# bb_header.net
KiCad netlist of a schematic drawn in Altium Designer
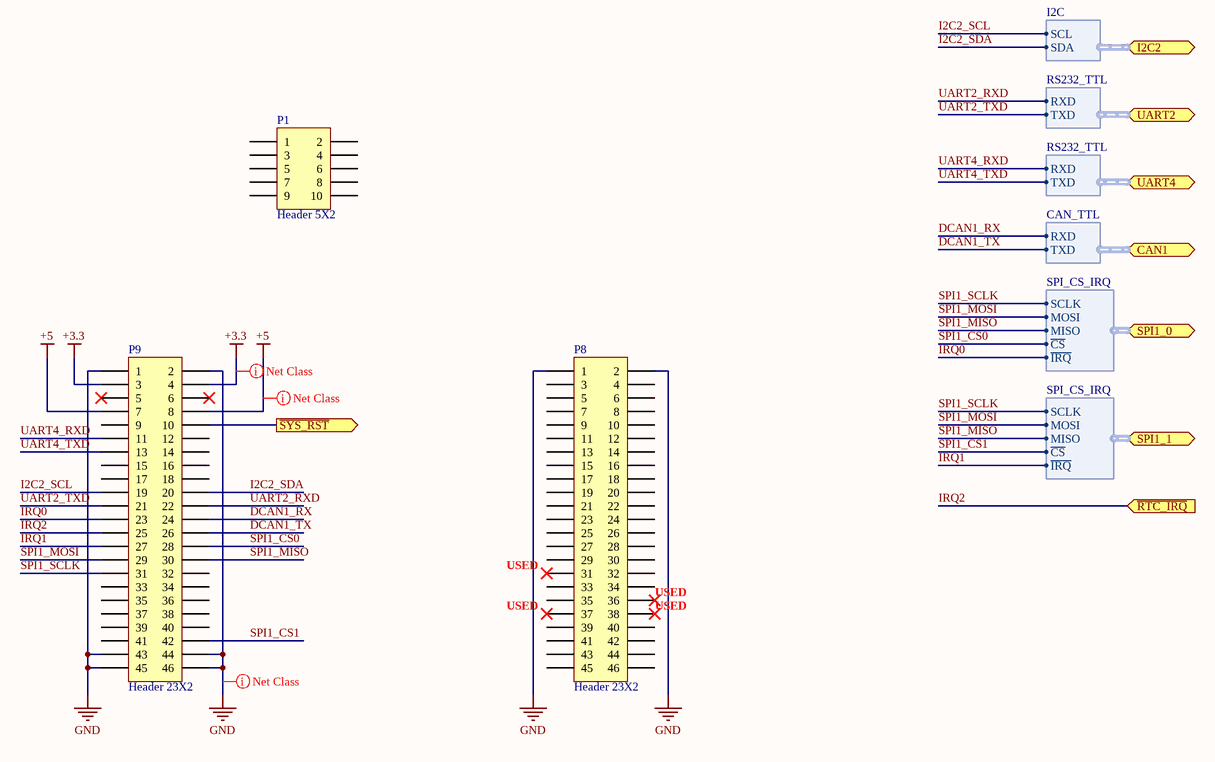
[diagram p0: bb header.SchDoc]

(export (version "E")
  (design (tool "Eeschema 10.0.6"))
  (components
    (comp (ref "P1")
      (value "Header 5X2")
      (footprint "TSW-105-07-T-D_DOWN")
      (description "Header, 5-Pin, Dual row")
      (fields (field (name "PUBLISHER") "Altium Limited"))
      (libsource (lib "Miscellaneous Connectors") (part "Header 5X2"))
    )
    (comp (ref "P8")
      (value "Header 23X2")
      (footprint "TSW-123-07-T-D_DOWN")
      (description "Header, 23-Pin, Dual row")
      (fields (field (name "PUBLISHER") "Altium Limited"))
      (libsource (lib "23x2 header") (part "Header 23X2"))
    )
    (comp (ref "P9")
      (value "Header 23X2")
      (footprint "TSW-123-07-T-D_DOWN")
      (description "Header, 23-Pin, Dual row")
      (fields (field (name "PUBLISHER") "Altium Limited"))
      (libsource (lib "23x2 header") (part "Header 23X2"))
    )
  )
  (nets
    (net (code "5") (name "+3.3") (class "Default")
      (node (ref "P9") (pin "3") (pinfunction "3_3") (pintype "passive"))
      (node (ref "P9") (pin "4") (pinfunction "4_4") (pintype "passive"))
    )
    (net (code "6") (name "+5") (class "Default")
      (node (ref "P9") (pin "7") (pinfunction "7_7") (pintype "passive"))
      (node (ref "P9") (pin "8") (pinfunction "8_8") (pintype "passive"))
    )
    (net (code "7") (name "/DCAN1_RX") (class "Default")
      (node (ref "P9") (pin "24") (pinfunction "24_24") (pintype "passive"))
    )
    (net (code "8") (name "/DCAN1_TX") (class "Default")
      (node (ref "P9") (pin "26") (pinfunction "26_26") (pintype "passive"))
    )
    (net (code "9") (name "/I2C2_SCL") (class "Default")
      (node (ref "P9") (pin "19") (pinfunction "19_19") (pintype "passive"))
    )
    (net (code "10") (name "/I2C2_SDA") (class "Default")
      (node (ref "P9") (pin "20") (pinfunction "20_20") (pintype "passive"))
    )
    (net (code "11") (name "/IRQ0") (class "Default")
      (node (ref "P9") (pin "23") (pinfunction "23_23") (pintype "passive"))
    )
    (net (code "12") (name "/IRQ1") (class "Default")
      (node (ref "P9") (pin "27") (pinfunction "27_27") (pintype "passive"))
    )
    (net (code "13") (name "/IRQ2") (class "Default")
      (node (ref "P9") (pin "25") (pinfunction "25_25") (pintype "passive"))
    )
    (net (code "14") (name "/SPI1_CS0") (class "Default")
      (node (ref "P9") (pin "28") (pinfunction "28_28") (pintype "passive"))
    )
    (net (code "15") (name "/SPI1_CS1") (class "Default")
      (node (ref "P9") (pin "42") (pinfunction "42_42") (pintype "passive"))
    )
    (net (code "16") (name "/SPI1_MISO") (class "Default")
      (node (ref "P9") (pin "30") (pinfunction "30_30") (pintype "passive"))
    )
    (net (code "17") (name "/SPI1_MOSI") (class "Default")
      (node (ref "P9") (pin "29") (pinfunction "29_29") (pintype "passive"))
    )
    (net (code "18") (name "/SPI1_SCLK") (class "Default")
      (node (ref "P9") (pin "31") (pinfunction "31_31") (pintype "passive"))
    )
    (net (code "19") (name "/UART2_RXD") (class "Default")
      (node (ref "P9") (pin "22") (pinfunction "22_22") (pintype "passive"))
    )
    (net (code "20") (name "/UART2_TXD") (class "Default")
      (node (ref "P9") (pin "21") (pinfunction "21_21") (pintype "passive"))
    )
    (net (code "21") (name "/UART4_RXD") (class "Default")
      (node (ref "P9") (pin "11") (pinfunction "11_11") (pintype "passive"))
    )
    (net (code "22") (name "/UART4_TXD") (class "Default")
      (node (ref "P9") (pin "13") (pinfunction "13_13") (pintype "passive"))
    )
    (net (code "27") (name "/~{SYS_RST}") (class "Default")
      (node (ref "P9") (pin "10") (pinfunction "10_10") (pintype "passive"))
    )
    (net (code "28") (name "GND") (class "Default")
      (node (ref "P8") (pin "1") (pinfunction "1_1") (pintype "passive"))
      (node (ref "P8") (pin "2") (pinfunction "2_2") (pintype "passive"))
      (node (ref "P9") (pin "1") (pinfunction "1_1") (pintype "passive"))
      (node (ref "P9") (pin "2") (pinfunction "2_2") (pintype "passive"))
      (node (ref "P9") (pin "43") (pinfunction "43_43") (pintype "passive"))
      (node (ref "P9") (pin "44") (pinfunction "44_44") (pintype "passive"))
      (node (ref "P9") (pin "45") (pinfunction "45_45") (pintype "passive"))
      (node (ref "P9") (pin "46") (pinfunction "46_46") (pintype "passive"))
    )
    (net (code "29") (name "unconnected-(P1-Pad1)") (class "Default")
      (node (ref "P1") (pin "1") (pinfunction "1_1") (pintype "passive"))
    )
    (net (code "30") (name "unconnected-(P1-Pad2)") (class "Default")
      (node (ref "P1") (pin "2") (pinfunction "2_2") (pintype "passive"))
    )
    (net (code "31") (name "unconnected-(P1-Pad3)") (class "Default")
      (node (ref "P1") (pin "3") (pinfunction "3_3") (pintype "passive"))
    )
    (net (code "32") (name "unconnected-(P1-Pad4)") (class "Default")
      (node (ref "P1") (pin "4") (pinfunction "4_4") (pintype "passive"))
    )
    (net (code "33") (name "unconnected-(P1-Pad5)") (class "Default")
      (node (ref "P1") (pin "5") (pinfunction "5_5") (pintype "passive"))
    )
    (net (code "34") (name "unconnected-(P1-Pad6)") (class "Default")
      (node (ref "P1") (pin "6") (pinfunction "6_6") (pintype "passive"))
    )
    (net (code "35") (name "unconnected-(P1-Pad7)") (class "Default")
      (node (ref "P1") (pin "7") (pinfunction "7_7") (pintype "passive"))
    )
    (net (code "36") (name "unconnected-(P1-Pad8)") (class "Default")
      (node (ref "P1") (pin "8") (pinfunction "8_8") (pintype "passive"))
    )
    (net (code "37") (name "unconnected-(P1-Pad9)") (class "Default")
      (node (ref "P1") (pin "9") (pinfunction "9_9") (pintype "passive"))
    )
    (net (code "38") (name "unconnected-(P1-Pad10)") (class "Default")
      (node (ref "P1") (pin "10") (pinfunction "10_10") (pintype "passive"))
    )
    (net (code "39") (name "unconnected-(P8-Pad3)") (class "Default")
      (node (ref "P8") (pin "3") (pinfunction "3_3") (pintype "passive"))
    )
    (net (code "40") (name "unconnected-(P8-Pad4)") (class "Default")
      (node (ref "P8") (pin "4") (pinfunction "4_4") (pintype "passive"))
    )
    (net (code "41") (name "unconnected-(P8-Pad5)") (class "Default")
      (node (ref "P8") (pin "5") (pinfunction "5_5") (pintype "passive"))
    )
    (net (code "42") (name "unconnected-(P8-Pad6)") (class "Default")
      (node (ref "P8") (pin "6") (pinfunction "6_6") (pintype "passive"))
    )
    (net (code "43") (name "unconnected-(P8-Pad7)") (class "Default")
      (node (ref "P8") (pin "7") (pinfunction "7_7") (pintype "passive"))
    )
    (net (code "44") (name "unconnected-(P8-Pad8)") (class "Default")
      (node (ref "P8") (pin "8") (pinfunction "8_8") (pintype "passive"))
    )
    (net (code "45") (name "unconnected-(P8-Pad9)") (class "Default")
      (node (ref "P8") (pin "9") (pinfunction "9_9") (pintype "passive"))
    )
    (net (code "46") (name "unconnected-(P8-Pad10)") (class "Default")
      (node (ref "P8") (pin "10") (pinfunction "10_10") (pintype "passive"))
    )
    (net (code "47") (name "unconnected-(P8-Pad11)") (class "Default")
      (node (ref "P8") (pin "11") (pinfunction "11_11") (pintype "passive"))
    )
    (net (code "48") (name "unconnected-(P8-Pad12)") (class "Default")
      (node (ref "P8") (pin "12") (pinfunction "12_12") (pintype "passive"))
    )
    (net (code "49") (name "unconnected-(P8-Pad13)") (class "Default")
      (node (ref "P8") (pin "13") (pinfunction "13_13") (pintype "passive"))
    )
    (net (code "50") (name "unconnected-(P8-Pad14)") (class "Default")
      (node (ref "P8") (pin "14") (pinfunction "14_14") (pintype "passive"))
    )
    (net (code "51") (name "unconnected-(P8-Pad15)") (class "Default")
      (node (ref "P8") (pin "15") (pinfunction "15_15") (pintype "passive"))
    )
    (net (code "52") (name "unconnected-(P8-Pad16)") (class "Default")
      (node (ref "P8") (pin "16") (pinfunction "16_16") (pintype "passive"))
    )
    (net (code "53") (name "unconnected-(P8-Pad17)") (class "Default")
      (node (ref "P8") (pin "17") (pinfunction "17_17") (pintype "passive"))
    )
    (net (code "54") (name "unconnected-(P8-Pad18)") (class "Default")
      (node (ref "P8") (pin "18") (pinfunction "18_18") (pintype "passive"))
    )
    (net (code "55") (name "unconnected-(P8-Pad19)") (class "Default")
      (node (ref "P8") (pin "19") (pinfunction "19_19") (pintype "passive"))
    )
    (net (code "56") (name "unconnected-(P8-Pad20)") (class "Default")
      (node (ref "P8") (pin "20") (pinfunction "20_20") (pintype "passive"))
    )
    (net (code "57") (name "unconnected-(P8-Pad21)") (class "Default")
      (node (ref "P8") (pin "21") (pinfunction "21_21") (pintype "passive"))
    )
    (net (code "58") (name "unconnected-(P8-Pad22)") (class "Default")
      (node (ref "P8") (pin "22") (pinfunction "22_22") (pintype "passive"))
    )
    (net (code "59") (name "unconnected-(P8-Pad23)") (class "Default")
      (node (ref "P8") (pin "23") (pinfunction "23_23") (pintype "passive"))
    )
    (net (code "60") (name "unconnected-(P8-Pad24)") (class "Default")
      (node (ref "P8") (pin "24") (pinfunction "24_24") (pintype "passive"))
    )
    (net (code "61") (name "unconnected-(P8-Pad25)") (class "Default")
      (node (ref "P8") (pin "25") (pinfunction "25_25") (pintype "passive"))
    )
    (net (code "62") (name "unconnected-(P8-Pad26)") (class "Default")
      (node (ref "P8") (pin "26") (pinfunction "26_26") (pintype "passive"))
    )
    (net (code "63") (name "unconnected-(P8-Pad27)") (class "Default")
      (node (ref "P8") (pin "27") (pinfunction "27_27") (pintype "passive"))
    )
    (net (code "64") (name "unconnected-(P8-Pad28)") (class "Default")
      (node (ref "P8") (pin "28") (pinfunction "28_28") (pintype "passive"))
    )
    (net (code "65") (name "unconnected-(P8-Pad29)") (class "Default")
      (node (ref "P8") (pin "29") (pinfunction "29_29") (pintype "passive"))
    )
    (net (code "66") (name "unconnected-(P8-Pad30)") (class "Default")
      (node (ref "P8") (pin "30") (pinfunction "30_30") (pintype "passive"))
    )
    (net (code "67") (name "unconnected-(P8-Pad31)") (class "Default")
      (node (ref "P8") (pin "31") (pinfunction "31_31") (pintype "passive+no_connect"))
    )
    (net (code "68") (name "unconnected-(P8-Pad32)") (class "Default")
      (node (ref "P8") (pin "32") (pinfunction "32_32") (pintype "passive"))
    )
    (net (code "69") (name "unconnected-(P8-Pad33)") (class "Default")
      (node (ref "P8") (pin "33") (pinfunction "33_33") (pintype "passive"))
    )
    (net (code "70") (name "unconnected-(P8-Pad34)") (class "Default")
      (node (ref "P8") (pin "34") (pinfunction "34_34") (pintype "passive"))
    )
    (net (code "71") (name "unconnected-(P8-Pad35)") (class "Default")
      (node (ref "P8") (pin "35") (pinfunction "35_35") (pintype "passive"))
    )
    (net (code "72") (name "unconnected-(P8-Pad36)") (class "Default")
      (node (ref "P8") (pin "36") (pinfunction "36_36") (pintype "passive+no_connect"))
    )
    (net (code "73") (name "unconnected-(P8-Pad37)") (class "Default")
      (node (ref "P8") (pin "37") (pinfunction "37_37") (pintype "passive+no_connect"))
    )
    (net (code "74") (name "unconnected-(P8-Pad38)") (class "Default")
      (node (ref "P8") (pin "38") (pinfunction "38_38") (pintype "passive+no_connect"))
    )
    (net (code "75") (name "unconnected-(P8-Pad39)") (class "Default")
      (node (ref "P8") (pin "39") (pinfunction "39_39") (pintype "passive"))
    )
    (net (code "76") (name "unconnected-(P8-Pad40)") (class "Default")
      (node (ref "P8") (pin "40") (pinfunction "40_40") (pintype "passive"))
    )
    (net (code "77") (name "unconnected-(P8-Pad41)") (class "Default")
      (node (ref "P8") (pin "41") (pinfunction "41_41") (pintype "passive"))
    )
    (net (code "78") (name "unconnected-(P8-Pad42)") (class "Default")
      (node (ref "P8") (pin "42") (pinfunction "42_42") (pintype "passive"))
    )
    (net (code "79") (name "unconnected-(P8-Pad43)") (class "Default")
      (node (ref "P8") (pin "43") (pinfunction "43_43") (pintype "passive"))
    )
    (net (code "80") (name "unconnected-(P8-Pad44)") (class "Default")
      (node (ref "P8") (pin "44") (pinfunction "44_44") (pintype "passive"))
    )
    (net (code "81") (name "unconnected-(P8-Pad45)") (class "Default")
      (node (ref "P8") (pin "45") (pinfunction "45_45") (pintype "passive"))
    )
    (net (code "82") (name "unconnected-(P8-Pad46)") (class "Default")
      (node (ref "P8") (pin "46") (pinfunction "46_46") (pintype "passive"))
    )
    (net (code "83") (name "unconnected-(P9-Pad5)") (class "Default")
      (node (ref "P9") (pin "5") (pinfunction "5_5") (pintype "passive+no_connect"))
    )
    (net (code "84") (name "unconnected-(P9-Pad6)") (class "Default")
      (node (ref "P9") (pin "6") (pinfunction "6_6") (pintype "passive+no_connect"))
    )
    (net (code "85") (name "unconnected-(P9-Pad9)") (class "Default")
      (node (ref "P9") (pin "9") (pinfunction "9_9") (pintype "passive"))
    )
    (net (code "86") (name "unconnected-(P9-Pad12)") (class "Default")
      (node (ref "P9") (pin "12") (pinfunction "12_12") (pintype "passive"))
    )
    (net (code "87") (name "unconnected-(P9-Pad14)") (class "Default")
      (node (ref "P9") (pin "14") (pinfunction "14_14") (pintype "passive"))
    )
    (net (code "88") (name "unconnected-(P9-Pad15)") (class "Default")
      (node (ref "P9") (pin "15") (pinfunction "15_15") (pintype "passive"))
    )
    (net (code "89") (name "unconnected-(P9-Pad16)") (class "Default")
      (node (ref "P9") (pin "16") (pinfunction "16_16") (pintype "passive"))
    )
    (net (code "90") (name "unconnected-(P9-Pad17)") (class "Default")
      (node (ref "P9") (pin "17") (pinfunction "17_17") (pintype "passive"))
    )
    (net (code "91") (name "unconnected-(P9-Pad18)") (class "Default")
      (node (ref "P9") (pin "18") (pinfunction "18_18") (pintype "passive"))
    )
    (net (code "92") (name "unconnected-(P9-Pad32)") (class "Default")
      (node (ref "P9") (pin "32") (pinfunction "32_32") (pintype "passive"))
    )
    (net (code "93") (name "unconnected-(P9-Pad33)") (class "Default")
      (node (ref "P9") (pin "33") (pinfunction "33_33") (pintype "passive"))
    )
    (net (code "94") (name "unconnected-(P9-Pad34)") (class "Default")
      (node (ref "P9") (pin "34") (pinfunction "34_34") (pintype "passive"))
    )
    (net (code "95") (name "unconnected-(P9-Pad35)") (class "Default")
      (node (ref "P9") (pin "35") (pinfunction "35_35") (pintype "passive"))
    )
    (net (code "96") (name "unconnected-(P9-Pad36)") (class "Default")
      (node (ref "P9") (pin "36") (pinfunction "36_36") (pintype "passive"))
    )
    (net (code "97") (name "unconnected-(P9-Pad37)") (class "Default")
      (node (ref "P9") (pin "37") (pinfunction "37_37") (pintype "passive"))
    )
    (net (code "98") (name "unconnected-(P9-Pad38)") (class "Default")
      (node (ref "P9") (pin "38") (pinfunction "38_38") (pintype "passive"))
    )
    (net (code "99") (name "unconnected-(P9-Pad39)") (class "Default")
      (node (ref "P9") (pin "39") (pinfunction "39_39") (pintype "passive"))
    )
    (net (code "100") (name "unconnected-(P9-Pad40)") (class "Default")
      (node (ref "P9") (pin "40") (pinfunction "40_40") (pintype "passive"))
    )
    (net (code "101") (name "unconnected-(P9-Pad41)") (class "Default")
      (node (ref "P9") (pin "41") (pinfunction "41_41") (pintype "passive"))
    )
  )
)
